# Nu_Module_Active_Base.net
KiCad netlist of a schematic drawn in EAGLE
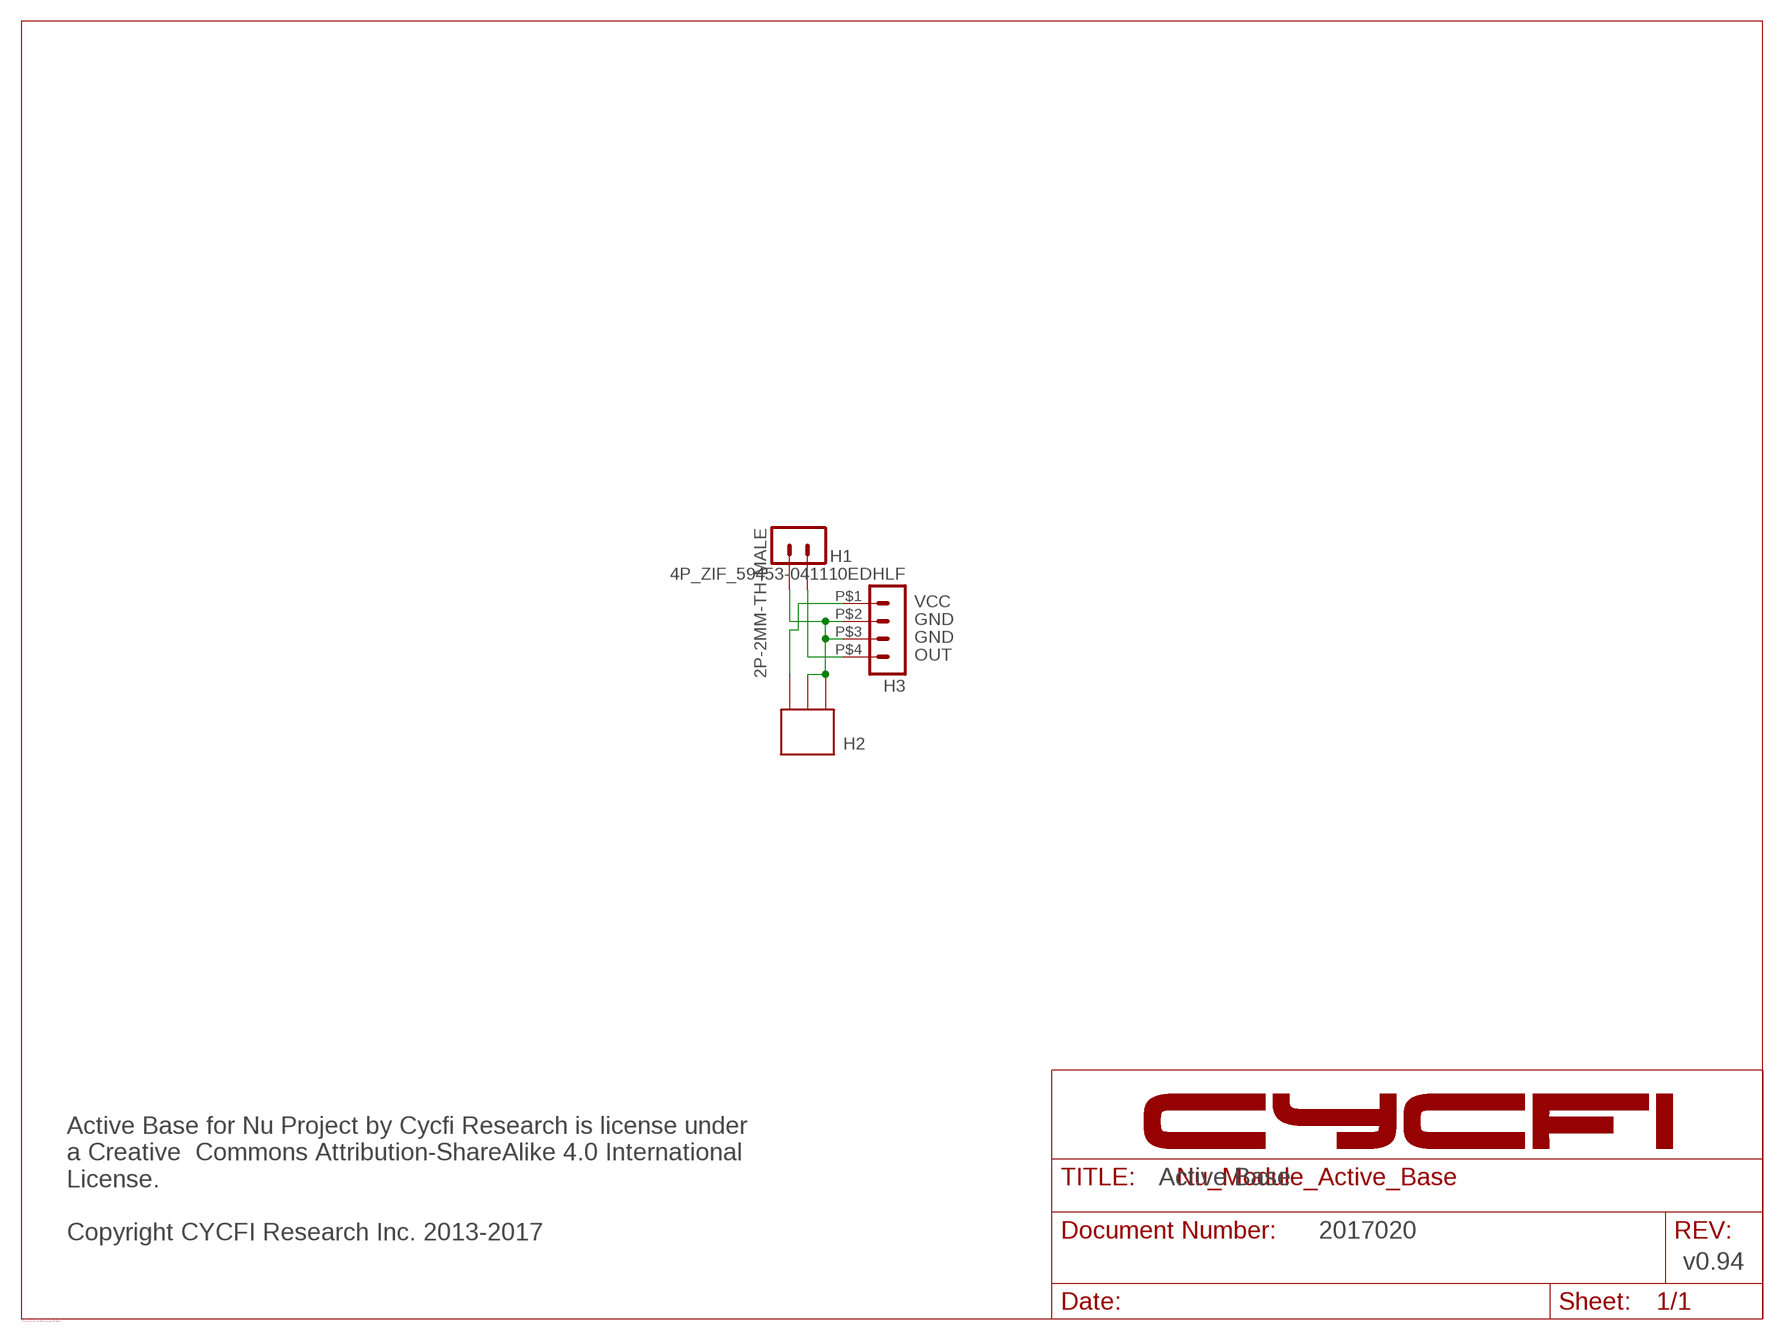
[diagram p0: schematic, sheet 1]

(export (version "E")
  (design (tool "Eeschema 10.0.6"))
  (components
    (comp (ref "H1")
      (value "2P-2MM-TH-MALE")
      (footprint "eagle-import:2P-2MM-TH")
      (libsource (lib "eagle-import") (part "2P-2MM-TH-MALE"))
    )
    (comp (ref "H2")
      (value "951102-8622-AR")
      (footprint "eagle-import:3P-TH-2MM")
      (libsource (lib "eagle-import") (part "951102-8622-AR"))
    )
    (comp (ref "H3")
      (value "4P_ZIF_59453-041110EDHLF")
      (footprint "eagle-import:4P_ZIF_59453-041110EDHLF")
      (libsource (lib "eagle-import") (part "4P_ZIF_59453-041110EDHLF"))
    )
  )
  (nets
    (net (code "1") (name "Net-(H1-1)") (class "Default")
      (node (ref "H1") (pin "P$1") (pinfunction "1_P$1") (pintype "passive"))
      (node (ref "H2") (pin "P$1") (pinfunction "P$1_P$1") (pintype "bidirectional"))
      (node (ref "H2") (pin "P$2") (pinfunction "P$2_P$2") (pintype "bidirectional"))
      (node (ref "H3") (pin "P$2") (pinfunction "2_P$2") (pintype "passive"))
      (node (ref "H3") (pin "P$3") (pinfunction "3_P$3") (pintype "passive"))
    )
    (net (code "2") (name "Net-(H1-2)") (class "Default")
      (node (ref "H1") (pin "P$2") (pinfunction "2_P$2") (pintype "passive"))
      (node (ref "H3") (pin "P$4") (pinfunction "4_P$4") (pintype "passive"))
    )
    (net (code "3") (name "Net-(H3-1)") (class "Default")
      (node (ref "H2") (pin "P$3") (pinfunction "P$3_P$3") (pintype "bidirectional"))
      (node (ref "H3") (pin "P$1") (pinfunction "1_P$1") (pintype "passive"))
    )
  )
)
